# SIDEPANEL3_2test.net
KiCad netlist of a schematic drawn in EAGLE
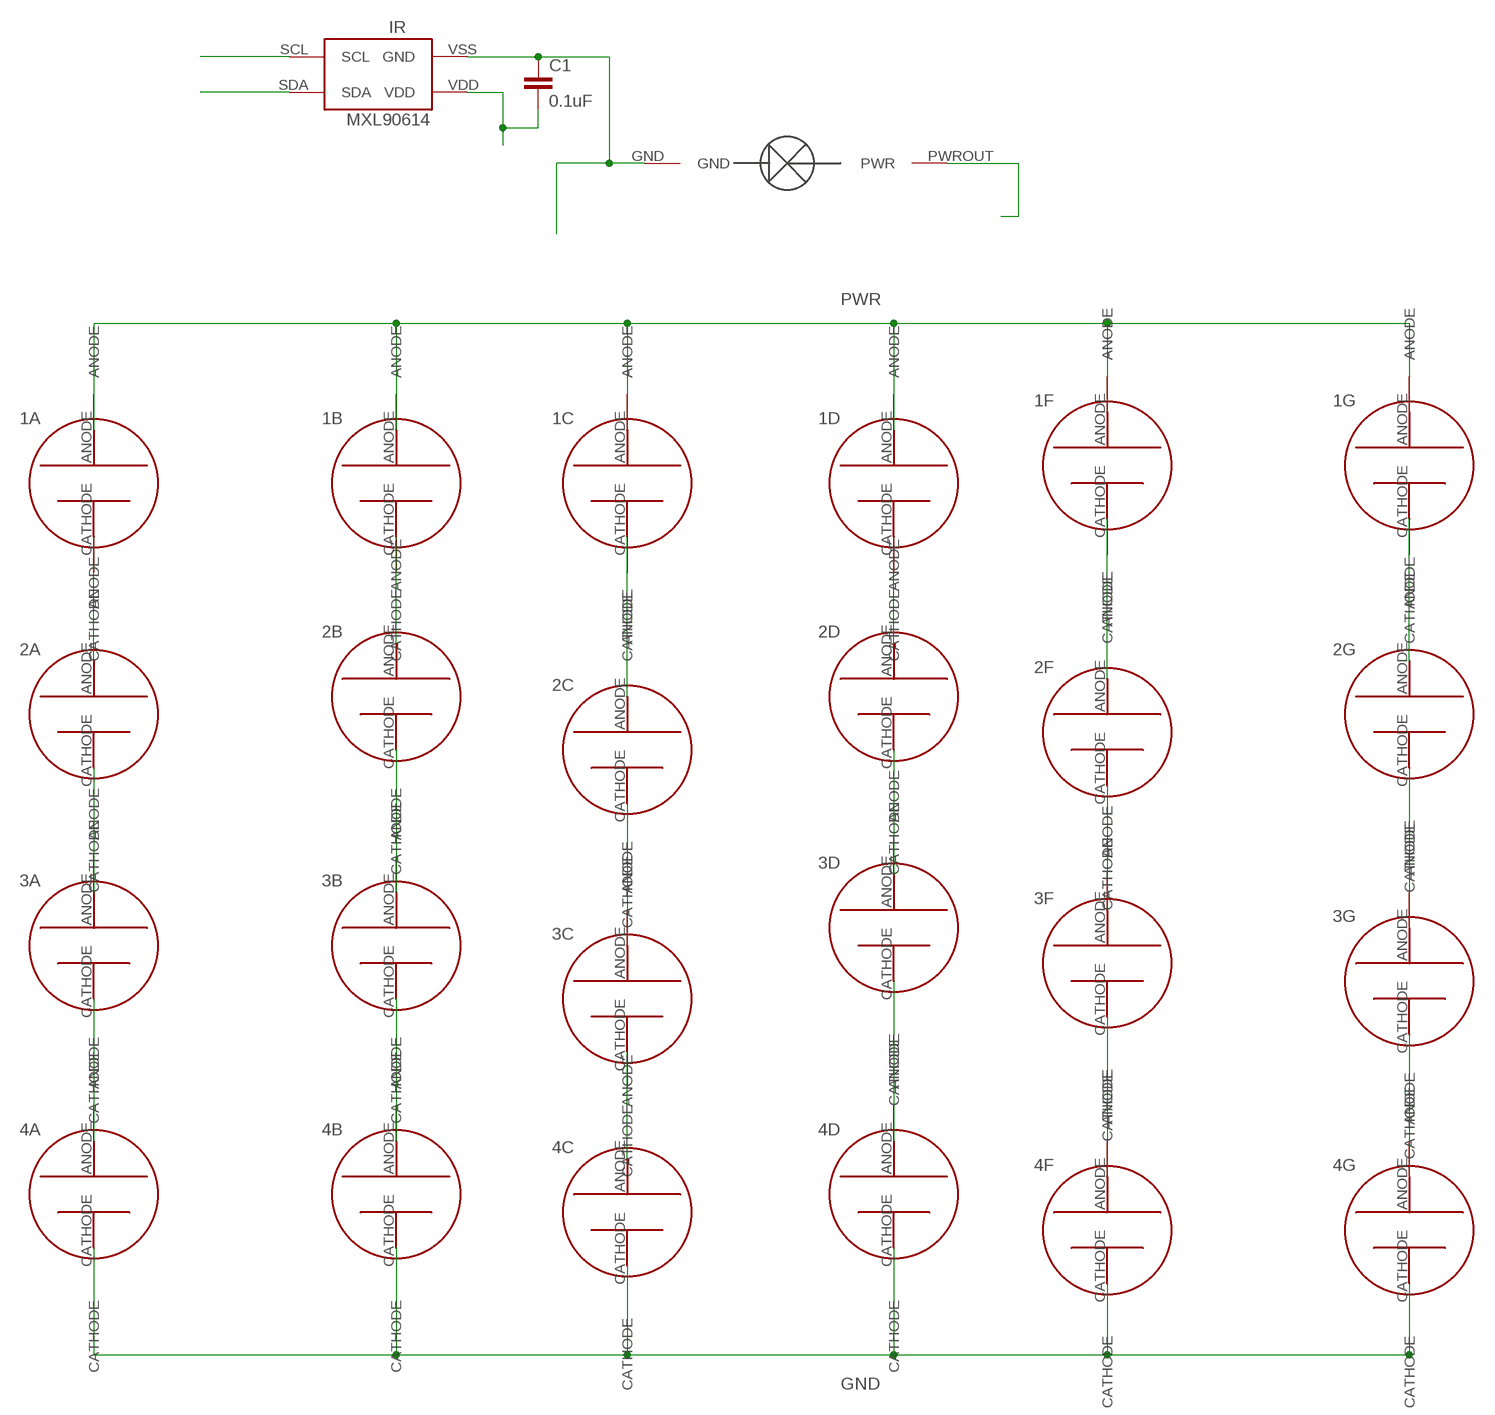
[diagram p0: schematic, sheet 1]

(export (version "E")
  (design (tool "Eeschema 10.0.6"))
  (components
    (comp (ref "1A")
      (value "NEWSOLARPANEL")
      (footprint "eagle-import:SOLARCELL2")
      (libsource (lib "eagle-import") (part "NEWSOLARPANEL"))
    )
    (comp (ref "1B")
      (value "NEWSOLARPANEL")
      (footprint "eagle-import:SOLARCELL2")
      (libsource (lib "eagle-import") (part "NEWSOLARPANEL"))
    )
    (comp (ref "1C")
      (value "NEWSOLARPANEL")
      (footprint "eagle-import:SOLARCELL2")
      (libsource (lib "eagle-import") (part "NEWSOLARPANEL"))
    )
    (comp (ref "1D")
      (value "NEWSOLARPANEL")
      (footprint "eagle-import:SOLARCELL2")
      (libsource (lib "eagle-import") (part "NEWSOLARPANEL"))
    )
    (comp (ref "1F")
      (value "NEWSOLARPANEL")
      (footprint "eagle-import:SOLARCELL2")
      (libsource (lib "eagle-import") (part "NEWSOLARPANEL"))
    )
    (comp (ref "1G")
      (value "NEWSOLARPANEL")
      (footprint "eagle-import:SOLARCELL2")
      (libsource (lib "eagle-import") (part "NEWSOLARPANEL"))
    )
    (comp (ref "2A")
      (value "NEWSOLARPANEL")
      (footprint "eagle-import:SOLARCELL2")
      (libsource (lib "eagle-import") (part "NEWSOLARPANEL"))
    )
    (comp (ref "2B")
      (value "NEWSOLARPANEL")
      (footprint "eagle-import:SOLARCELL2")
      (libsource (lib "eagle-import") (part "NEWSOLARPANEL"))
    )
    (comp (ref "2C")
      (value "NEWSOLARPANEL")
      (footprint "eagle-import:SOLARCELL2")
      (libsource (lib "eagle-import") (part "NEWSOLARPANEL"))
    )
    (comp (ref "2D")
      (value "NEWSOLARPANEL")
      (footprint "eagle-import:SOLARCELL2")
      (libsource (lib "eagle-import") (part "NEWSOLARPANEL"))
    )
    (comp (ref "2F")
      (value "NEWSOLARPANEL")
      (footprint "eagle-import:SOLARCELL2")
      (libsource (lib "eagle-import") (part "NEWSOLARPANEL"))
    )
    (comp (ref "2G")
      (value "NEWSOLARPANEL")
      (footprint "eagle-import:SOLARCELL2")
      (libsource (lib "eagle-import") (part "NEWSOLARPANEL"))
    )
    (comp (ref "3A")
      (value "NEWSOLARPANEL")
      (footprint "eagle-import:SOLARCELL2")
      (libsource (lib "eagle-import") (part "NEWSOLARPANEL"))
    )
    (comp (ref "3B")
      (value "NEWSOLARPANEL")
      (footprint "eagle-import:SOLARCELL2")
      (libsource (lib "eagle-import") (part "NEWSOLARPANEL"))
    )
    (comp (ref "3C")
      (value "NEWSOLARPANEL")
      (footprint "eagle-import:SOLARCELL2")
      (libsource (lib "eagle-import") (part "NEWSOLARPANEL"))
    )
    (comp (ref "3D")
      (value "NEWSOLARPANEL")
      (footprint "eagle-import:SOLARCELL2")
      (libsource (lib "eagle-import") (part "NEWSOLARPANEL"))
    )
    (comp (ref "3F")
      (value "NEWSOLARPANEL")
      (footprint "eagle-import:SOLARCELL2")
      (libsource (lib "eagle-import") (part "NEWSOLARPANEL"))
    )
    (comp (ref "3G")
      (value "NEWSOLARPANEL")
      (footprint "eagle-import:SOLARCELL2")
      (libsource (lib "eagle-import") (part "NEWSOLARPANEL"))
    )
    (comp (ref "4A")
      (value "NEWSOLARPANEL")
      (footprint "eagle-import:SOLARCELL2")
      (libsource (lib "eagle-import") (part "NEWSOLARPANEL"))
    )
    (comp (ref "4B")
      (value "NEWSOLARPANEL")
      (footprint "eagle-import:SOLARCELL2")
      (libsource (lib "eagle-import") (part "NEWSOLARPANEL"))
    )
    (comp (ref "4C")
      (value "NEWSOLARPANEL")
      (footprint "eagle-import:SOLARCELL2")
      (libsource (lib "eagle-import") (part "NEWSOLARPANEL"))
    )
    (comp (ref "4D")
      (value "NEWSOLARPANEL")
      (footprint "eagle-import:SOLARCELL2")
      (libsource (lib "eagle-import") (part "NEWSOLARPANEL"))
    )
    (comp (ref "4F")
      (value "NEWSOLARPANEL")
      (footprint "eagle-import:SOLARCELL2")
      (libsource (lib "eagle-import") (part "NEWSOLARPANEL"))
    )
    (comp (ref "4G")
      (value "NEWSOLARPANEL")
      (footprint "eagle-import:SOLARCELL2")
      (libsource (lib "eagle-import") (part "NEWSOLARPANEL"))
    )
    (comp (ref "C1")
      (value "0.1uF")
      (footprint "eagle-import:0805")
      (libsource (lib "eagle-import") (part "CAP0805"))
    )
    (comp (ref "IR")
      (value "MXL90620")
      (footprint "eagle-import:MXL90614")
      (libsource (lib "eagle-import") (part "MXL90620"))
    )
    (comp (ref "U$1")
      (value "PHOTODETECTOR")
      (footprint "eagle-import:PHOTODECTORDEVICE2")
      (libsource (lib "eagle-import") (part "PHOTODETECTOR"))
    )
  )
  (nets
    (net (code "1") (name "/GND") (class "Default")
      (node (ref "4A") (pin "CATHODE") (pinfunction "CATHODE_CATHODE") (pintype "bidirectional"))
      (node (ref "4B") (pin "CATHODE") (pinfunction "CATHODE_CATHODE") (pintype "bidirectional"))
      (node (ref "4C") (pin "CATHODE") (pinfunction "CATHODE_CATHODE") (pintype "bidirectional"))
      (node (ref "4D") (pin "CATHODE") (pinfunction "CATHODE_CATHODE") (pintype "bidirectional"))
      (node (ref "4F") (pin "CATHODE") (pinfunction "CATHODE_CATHODE") (pintype "bidirectional"))
      (node (ref "4G") (pin "CATHODE") (pinfunction "CATHODE_CATHODE") (pintype "bidirectional"))
      (node (ref "C1") (pin "1") (pinfunction "1_1") (pintype "passive"))
      (node (ref "IR") (pin "VSS") (pinfunction "GND_VSS") (pintype "bidirectional"))
      (node (ref "U$1") (pin "GND") (pinfunction "GND_GND") (pintype "bidirectional"))
    )
    (net (code "2") (name "/PWR") (class "Default")
      (node (ref "1A") (pin "ANODE") (pinfunction "ANODE_ANODE") (pintype "bidirectional"))
      (node (ref "1B") (pin "ANODE") (pinfunction "ANODE_ANODE") (pintype "bidirectional"))
      (node (ref "1C") (pin "ANODE") (pinfunction "ANODE_ANODE") (pintype "bidirectional"))
      (node (ref "1D") (pin "ANODE") (pinfunction "ANODE_ANODE") (pintype "bidirectional"))
      (node (ref "1F") (pin "ANODE") (pinfunction "ANODE_ANODE") (pintype "bidirectional"))
      (node (ref "1G") (pin "ANODE") (pinfunction "ANODE_ANODE") (pintype "bidirectional"))
    )
    (net (code "3") (name "Net-(1A-PadCATHODE)") (class "Default")
      (node (ref "1A") (pin "CATHODE") (pinfunction "CATHODE_CATHODE") (pintype "bidirectional"))
      (node (ref "2A") (pin "ANODE") (pinfunction "ANODE_ANODE") (pintype "bidirectional"))
    )
    (net (code "4") (name "Net-(1B-PadCATHODE)") (class "Default")
      (node (ref "1B") (pin "CATHODE") (pinfunction "CATHODE_CATHODE") (pintype "bidirectional"))
      (node (ref "2B") (pin "ANODE") (pinfunction "ANODE_ANODE") (pintype "bidirectional"))
    )
    (net (code "5") (name "Net-(1C-PadCATHODE)") (class "Default")
      (node (ref "1C") (pin "CATHODE") (pinfunction "CATHODE_CATHODE") (pintype "bidirectional"))
      (node (ref "2C") (pin "ANODE") (pinfunction "ANODE_ANODE") (pintype "bidirectional"))
    )
    (net (code "6") (name "Net-(1D-PadCATHODE)") (class "Default")
      (node (ref "1D") (pin "CATHODE") (pinfunction "CATHODE_CATHODE") (pintype "bidirectional"))
      (node (ref "2D") (pin "ANODE") (pinfunction "ANODE_ANODE") (pintype "bidirectional"))
    )
    (net (code "7") (name "Net-(1F-PadCATHODE)") (class "Default")
      (node (ref "1F") (pin "CATHODE") (pinfunction "CATHODE_CATHODE") (pintype "bidirectional"))
      (node (ref "2F") (pin "ANODE") (pinfunction "ANODE_ANODE") (pintype "bidirectional"))
    )
    (net (code "8") (name "Net-(1G-PadCATHODE)") (class "Default")
      (node (ref "1G") (pin "CATHODE") (pinfunction "CATHODE_CATHODE") (pintype "bidirectional"))
      (node (ref "2G") (pin "ANODE") (pinfunction "ANODE_ANODE") (pintype "bidirectional"))
    )
    (net (code "9") (name "Net-(2A-PadCATHODE)") (class "Default")
      (node (ref "2A") (pin "CATHODE") (pinfunction "CATHODE_CATHODE") (pintype "bidirectional"))
      (node (ref "3A") (pin "ANODE") (pinfunction "ANODE_ANODE") (pintype "bidirectional"))
    )
    (net (code "10") (name "Net-(2B-PadCATHODE)") (class "Default")
      (node (ref "2B") (pin "CATHODE") (pinfunction "CATHODE_CATHODE") (pintype "bidirectional"))
      (node (ref "3B") (pin "ANODE") (pinfunction "ANODE_ANODE") (pintype "bidirectional"))
    )
    (net (code "11") (name "Net-(2C-PadCATHODE)") (class "Default")
      (node (ref "2C") (pin "CATHODE") (pinfunction "CATHODE_CATHODE") (pintype "bidirectional"))
      (node (ref "3C") (pin "ANODE") (pinfunction "ANODE_ANODE") (pintype "bidirectional"))
    )
    (net (code "12") (name "Net-(2D-PadCATHODE)") (class "Default")
      (node (ref "2D") (pin "CATHODE") (pinfunction "CATHODE_CATHODE") (pintype "bidirectional"))
      (node (ref "3D") (pin "ANODE") (pinfunction "ANODE_ANODE") (pintype "bidirectional"))
    )
    (net (code "13") (name "Net-(2F-PadCATHODE)") (class "Default")
      (node (ref "2F") (pin "CATHODE") (pinfunction "CATHODE_CATHODE") (pintype "bidirectional"))
      (node (ref "3F") (pin "ANODE") (pinfunction "ANODE_ANODE") (pintype "bidirectional"))
    )
    (net (code "14") (name "Net-(2G-PadCATHODE)") (class "Default")
      (node (ref "2G") (pin "CATHODE") (pinfunction "CATHODE_CATHODE") (pintype "bidirectional"))
      (node (ref "3G") (pin "ANODE") (pinfunction "ANODE_ANODE") (pintype "bidirectional"))
    )
    (net (code "15") (name "Net-(3A-PadCATHODE)") (class "Default")
      (node (ref "3A") (pin "CATHODE") (pinfunction "CATHODE_CATHODE") (pintype "bidirectional"))
      (node (ref "4A") (pin "ANODE") (pinfunction "ANODE_ANODE") (pintype "bidirectional"))
    )
    (net (code "16") (name "Net-(3B-PadCATHODE)") (class "Default")
      (node (ref "3B") (pin "CATHODE") (pinfunction "CATHODE_CATHODE") (pintype "bidirectional"))
      (node (ref "4B") (pin "ANODE") (pinfunction "ANODE_ANODE") (pintype "bidirectional"))
    )
    (net (code "17") (name "Net-(3C-PadCATHODE)") (class "Default")
      (node (ref "3C") (pin "CATHODE") (pinfunction "CATHODE_CATHODE") (pintype "bidirectional"))
      (node (ref "4C") (pin "ANODE") (pinfunction "ANODE_ANODE") (pintype "bidirectional"))
    )
    (net (code "18") (name "Net-(3D-PadCATHODE)") (class "Default")
      (node (ref "3D") (pin "CATHODE") (pinfunction "CATHODE_CATHODE") (pintype "bidirectional"))
      (node (ref "4D") (pin "ANODE") (pinfunction "ANODE_ANODE") (pintype "bidirectional"))
    )
    (net (code "19") (name "Net-(3F-PadCATHODE)") (class "Default")
      (node (ref "3F") (pin "CATHODE") (pinfunction "CATHODE_CATHODE") (pintype "bidirectional"))
      (node (ref "4F") (pin "ANODE") (pinfunction "ANODE_ANODE") (pintype "bidirectional"))
    )
    (net (code "20") (name "Net-(3G-PadCATHODE)") (class "Default")
      (node (ref "3G") (pin "CATHODE") (pinfunction "CATHODE_CATHODE") (pintype "bidirectional"))
      (node (ref "4G") (pin "ANODE") (pinfunction "ANODE_ANODE") (pintype "bidirectional"))
    )
    (net (code "21") (name "Net-(C1-Pad2)") (class "Default")
      (node (ref "C1") (pin "2") (pinfunction "2_2") (pintype "passive"))
      (node (ref "IR") (pin "VDD") (pinfunction "VDD_VDD") (pintype "bidirectional"))
    )
    (net (code "22") (name "unconnected-(IR-PadSCL)") (class "Default")
      (node (ref "IR") (pin "SCL") (pinfunction "SCL_SCL") (pintype "bidirectional"))
    )
    (net (code "23") (name "unconnected-(IR-PadSDA)") (class "Default")
      (node (ref "IR") (pin "SDA") (pinfunction "SDA_SDA") (pintype "bidirectional"))
    )
    (net (code "24") (name "unconnected-(U$1-PWR-PadPWROUT)") (class "Default")
      (node (ref "U$1") (pin "PWROUT") (pinfunction "PWR_PWROUT") (pintype "bidirectional"))
    )
  )
)
